# LTE.net
KiCad netlist of a schematic drawn in Altium Designer
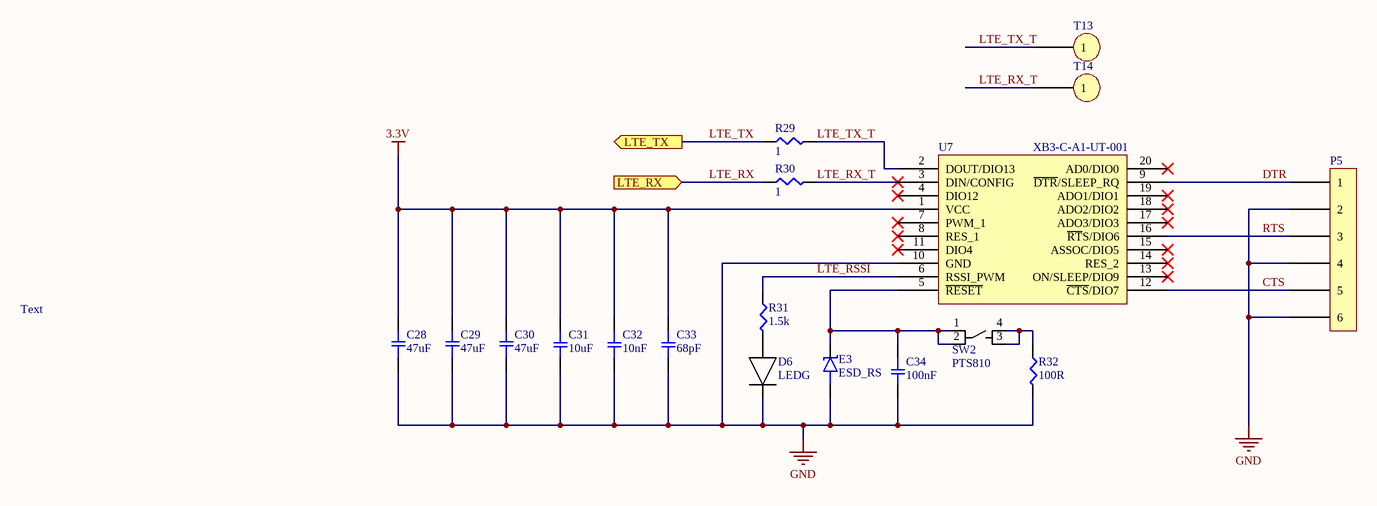
[diagram p0: LTE.SchDoc]

(export (version "E")
  (design (tool "Eeschema 10.0.6"))
  (components
    (comp (ref "C28")
      (value "47uF")
      (footprint "0805-CAP")
      (libsource (lib "passive components") (part "0805C 47UF"))
    )
    (comp (ref "C29")
      (value "47uF")
      (footprint "0805-CAP")
      (libsource (lib "passive components") (part "0805C 47UF"))
    )
    (comp (ref "C30")
      (value "47uF")
      (footprint "0805-CAP")
      (libsource (lib "passive components") (part "0805C 47UF"))
    )
    (comp (ref "C31")
      (value "10uF")
      (footprint "0603-CAP")
      (fields (field (name "Comment") "0603C 10UF"))
      (libsource (lib "passive components") (part "0603C 10UF"))
    )
    (comp (ref "C32")
      (value "10nF")
      (footprint "0603-CAP")
      (fields (field (name "Comment") "0603C 10NF"))
      (libsource (lib "passive components") (part "0603C 10NF"))
    )
    (comp (ref "C33")
      (value "68pF")
      (footprint "0603-CAP")
      (fields (field (name "Comment") "0603C 68PF"))
      (libsource (lib "passive components") (part "0603C 68PF"))
    )
    (comp (ref "C34")
      (value "100nF")
      (footprint "0603-CAP")
      (fields (field (name "Comment") "0603C 100NF"))
      (libsource (lib "passive components") (part "0603C 100NF"))
    )
    (comp (ref "D6")
      (value "LEDG")
      (footprint "0603-LED")
      (libsource (lib "passive components") (part "0603 LEDG"))
    )
    (comp (ref "E3")
      (value "ESD_RS")
      (footprint "ESD_RS")
      (libsource (lib "passive components") (part "ESD_RESET"))
    )
    (comp (ref "P5")
      (value "6pins_connector")
      (footprint "6_PINS_2.54")
      (libsource (lib "2.54_Connectors") (part "6pins_connector"))
    )
    (comp (ref "R29")
      (value "1")
      (footprint "0603-RES")
      (fields (field (name "Comment") "0603R 1R"))
      (libsource (lib "passive components") (part "0603R 1R"))
    )
    (comp (ref "R30")
      (value "1")
      (footprint "0603-RES")
      (fields (field (name "Comment") "0603R 1R"))
      (libsource (lib "passive components") (part "0603R 1R"))
    )
    (comp (ref "R31")
      (value "1.5k")
      (footprint "0603-RES")
      (fields (field (name "Comment") "0603R 1K5R"))
      (libsource (lib "passive components") (part "0603R 1K5R"))
    )
    (comp (ref "R32")
      (value "100R")
      (footprint "0603-RES")
      (fields (field (name "Comment") "0603R 100R"))
      (libsource (lib "passive components") (part "0603R 100R"))
    )
    (comp (ref "SW2")
      (value "PTS810")
      (footprint "PTS810_SJM_250_SMTR_LFS:*SW_PTS810_SJM_250_SMTR_LFS")
      (description "Tactile Switch SPST-NO Top Actuated Surface Mount")
      (fields (field (name "MP") "PTS810 SJM 250 SMTR LFS") (field (name "MF") "C&K"))
      (libsource (lib "PTS810_SJM_250_SMTR_LFS") (part "PTS810_SJM_250_SMTR_LFS"))
    )
    (comp (ref "T13") (value "*") (footprint "1_PIN_test") (libsource (lib "*") (part "1pin_header")))
    (comp (ref "T14") (value "*") (footprint "1_PIN_test") (libsource (lib "*") (part "1pin_header")))
    (comp (ref "U7")
      (value "XB3-C-A1-UT-001")
      (footprint "XB24CAPIT-001")
      (fields (field (name "DIGIKEY PART NUMBER") "602-2211-ND") (field (name "MF") "Digi"))
      (libsource (lib "XBee_LTE") (part "XB3-C-A1-UT-001"))
    )
  )
  (nets
    (net (code "1") (name "/CTS") (class "Default")
      (node (ref "P5") (pin "5") (pinfunction "5_5") (pintype "passive"))
      (node (ref "U7") (pin "12") (pinfunction "~{CTS}/DIO7_12") (pintype "passive"))
    )
    (net (code "2") (name "/DTR") (class "Default")
      (node (ref "P5") (pin "1") (pinfunction "1_1") (pintype "passive"))
      (node (ref "U7") (pin "9") (pinfunction "~{DTR}/SLEEP_RQ_9") (pintype "passive"))
    )
    (net (code "3") (name "/LTE_RSSI") (class "Default")
      (node (ref "R31") (pin "1") (pinfunction "1_1") (pintype "passive"))
      (node (ref "U7") (pin "6") (pinfunction "RSSI_PWM_6") (pintype "passive"))
    )
    (net (code "4") (name "/LTE_RX") (class "Default")
      (node (ref "R30") (pin "1") (pinfunction "1_1") (pintype "passive"))
    )
    (net (code "5") (name "/LTE_RX_T") (class "Default")
      (node (ref "R30") (pin "2") (pinfunction "2_2") (pintype "passive"))
      (node (ref "T14") (pin "1") (pinfunction "1_1") (pintype "passive"))
      (node (ref "U7") (pin "3") (pinfunction "DIN/CONFIG_3") (pintype "passive"))
    )
    (net (code "6") (name "/LTE_TX") (class "Default")
      (node (ref "R29") (pin "1") (pinfunction "1_1") (pintype "passive"))
    )
    (net (code "7") (name "/LTE_TX_T") (class "Default")
      (node (ref "R29") (pin "2") (pinfunction "2_2") (pintype "passive"))
      (node (ref "T13") (pin "1") (pinfunction "1_1") (pintype "passive"))
      (node (ref "U7") (pin "2") (pinfunction "DOUT/DIO13_2") (pintype "passive"))
    )
    (net (code "8") (name "/RTS") (class "Default")
      (node (ref "P5") (pin "3") (pinfunction "3_3") (pintype "passive"))
      (node (ref "U7") (pin "16") (pinfunction "~{RT}S/DIO6_16") (pintype "passive"))
    )
    (net (code "9") (name "3.3V") (class "Default")
      (node (ref "C28") (pin "2") (pinfunction "2_2") (pintype "passive"))
      (node (ref "C29") (pin "2") (pinfunction "2_2") (pintype "passive"))
      (node (ref "C30") (pin "2") (pinfunction "2_2") (pintype "passive"))
      (node (ref "C31") (pin "1") (pinfunction "1_1") (pintype "passive"))
      (node (ref "C32") (pin "1") (pinfunction "1_1") (pintype "passive"))
      (node (ref "C33") (pin "1") (pinfunction "1_1") (pintype "passive"))
      (node (ref "U7") (pin "1") (pinfunction "VCC_1") (pintype "passive"))
    )
    (net (code "10") (name "GND") (class "Default")
      (node (ref "C28") (pin "1") (pinfunction "1_1") (pintype "passive"))
      (node (ref "C29") (pin "1") (pinfunction "1_1") (pintype "passive"))
      (node (ref "C30") (pin "1") (pinfunction "1_1") (pintype "passive"))
      (node (ref "C31") (pin "2") (pinfunction "2_2") (pintype "passive"))
      (node (ref "C32") (pin "2") (pinfunction "2_2") (pintype "passive"))
      (node (ref "C33") (pin "2") (pinfunction "2_2") (pintype "passive"))
      (node (ref "C34") (pin "2") (pinfunction "2_2") (pintype "passive"))
      (node (ref "D6") (pin "2") (pinfunction "2_2") (pintype "passive"))
      (node (ref "E3") (pin "2") (pinfunction "2_2") (pintype "passive"))
      (node (ref "P5") (pin "2") (pinfunction "2_2") (pintype "passive"))
      (node (ref "P5") (pin "4") (pinfunction "4_4") (pintype "passive"))
      (node (ref "P5") (pin "6") (pinfunction "6_6") (pintype "passive"))
      (node (ref "R32") (pin "2") (pinfunction "2_2") (pintype "passive"))
      (node (ref "U7") (pin "10") (pinfunction "GND_10") (pintype "passive"))
    )
    (net (code "11") (name "Net-(D6-Pad1)") (class "Default")
      (node (ref "D6") (pin "1") (pinfunction "1_1") (pintype "passive"))
      (node (ref "R31") (pin "2") (pinfunction "2_2") (pintype "passive"))
    )
    (net (code "12") (name "Net-(R32-Pad1)") (class "Default")
      (node (ref "R32") (pin "1") (pinfunction "1_1") (pintype "passive"))
      (node (ref "SW2") (pin "3") (pinfunction "3_3") (pintype "passive"))
      (node (ref "SW2") (pin "4") (pinfunction "4_4") (pintype "passive"))
    )
    (net (code "13") (name "Net-(U7-~{RESET})") (class "Default")
      (node (ref "C34") (pin "1") (pinfunction "1_1") (pintype "passive"))
      (node (ref "E3") (pin "1") (pinfunction "1_1") (pintype "passive"))
      (node (ref "SW2") (pin "1") (pinfunction "1_1") (pintype "passive"))
      (node (ref "SW2") (pin "2") (pinfunction "2_2") (pintype "passive"))
      (node (ref "U7") (pin "5") (pinfunction "~{RESET}_5") (pintype "passive"))
    )
    (net (code "14") (name "unconnected-(U7-AD0{slash}DIO0-Pad20)") (class "Default")
      (node (ref "U7") (pin "20") (pinfunction "AD0/DIO0_20") (pintype "passive+no_connect"))
    )
    (net (code "15") (name "unconnected-(U7-ADO1{slash}DIO1-Pad19)") (class "Default")
      (node (ref "U7") (pin "19") (pinfunction "ADO1/DIO1_19") (pintype "passive+no_connect"))
    )
    (net (code "16") (name "unconnected-(U7-ADO2{slash}DIO2-Pad18)") (class "Default")
      (node (ref "U7") (pin "18") (pinfunction "ADO2/DIO2_18") (pintype "passive+no_connect"))
    )
    (net (code "17") (name "unconnected-(U7-ADO3{slash}DIO3-Pad17)") (class "Default")
      (node (ref "U7") (pin "17") (pinfunction "ADO3/DIO3_17") (pintype "passive+no_connect"))
    )
    (net (code "18") (name "unconnected-(U7-ASSOC{slash}DIO5-Pad15)") (class "Default")
      (node (ref "U7") (pin "15") (pinfunction "ASSOC/DIO5_15") (pintype "passive+no_connect"))
    )
    (net (code "19") (name "unconnected-(U7-DIO4-Pad11)") (class "Default")
      (node (ref "U7") (pin "11") (pinfunction "DIO4_11") (pintype "passive+no_connect"))
    )
    (net (code "20") (name "unconnected-(U7-DIO12-Pad4)") (class "Default")
      (node (ref "U7") (pin "4") (pinfunction "DIO12_4") (pintype "passive+no_connect"))
    )
    (net (code "21") (name "unconnected-(U7-ON{slash}SLEEP{slash}DIO9-Pad13)") (class "Default")
      (node (ref "U7") (pin "13") (pinfunction "ON/SLEEP/DIO9_13") (pintype "passive+no_connect"))
    )
    (net (code "22") (name "unconnected-(U7-PWM_1-Pad7)") (class "Default")
      (node (ref "U7") (pin "7") (pinfunction "PWM_1_7") (pintype "passive+no_connect"))
    )
    (net (code "23") (name "unconnected-(U7-RES_1-Pad8)") (class "Default")
      (node (ref "U7") (pin "8") (pinfunction "RES_1_8") (pintype "passive+no_connect"))
    )
    (net (code "24") (name "unconnected-(U7-RES_2-Pad14)") (class "Default")
      (node (ref "U7") (pin "14") (pinfunction "RES_2_14") (pintype "passive+no_connect"))
    )
  )
)
